# blinkm_mk2v5a.net
KiCad netlist of a schematic drawn in EAGLE
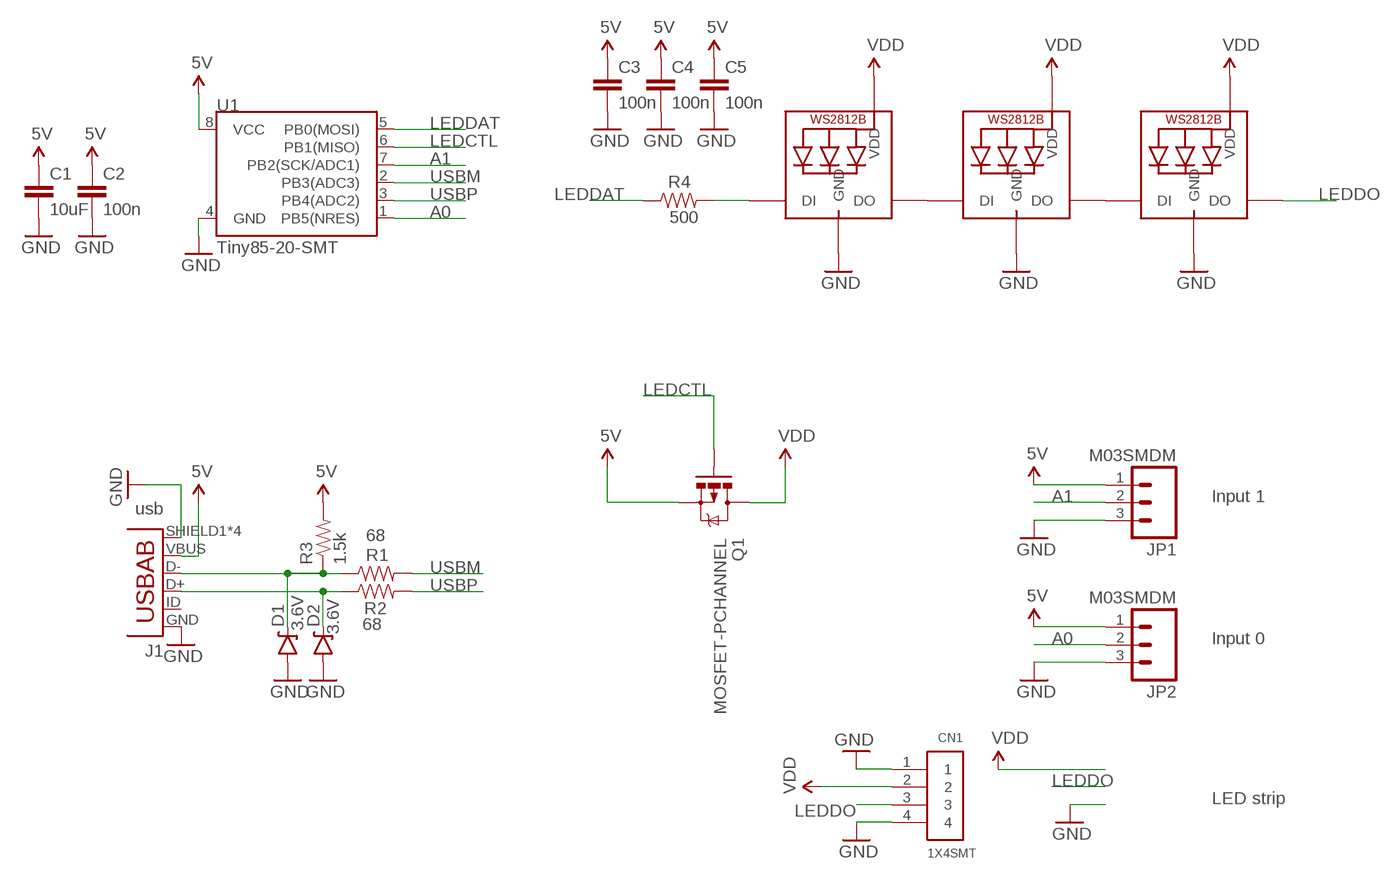
[diagram p0: schematic, sheet 1]

(export (version "E")
  (design (tool "Eeschema 10.0.6"))
  (components
    (comp (ref "C1")
      (value "10uF")
      (footprint "eagle-import:0603-CAP")
      (libsource (lib "eagle-import") (part "CAP0603-CAP"))
    )
    (comp (ref "C2")
      (value "100n")
      (footprint "eagle-import:0603-CAP")
      (libsource (lib "eagle-import") (part "CAP0603-CAP"))
    )
    (comp (ref "C3")
      (value "100n")
      (footprint "eagle-import:0603-CAP")
      (libsource (lib "eagle-import") (part "CAP0603-CAP"))
    )
    (comp (ref "C4")
      (value "100n")
      (footprint "eagle-import:0603-CAP")
      (libsource (lib "eagle-import") (part "CAP0603-CAP"))
    )
    (comp (ref "C5")
      (value "100n")
      (footprint "eagle-import:0603-CAP")
      (libsource (lib "eagle-import") (part "CAP0603-CAP"))
    )
    (comp (ref "CN1")
      (value "1X4SMT")
      (footprint "eagle-import:1X4-SMT")
      (libsource (lib "eagle-import") (part "1X4SMT"))
    )
    (comp (ref "D1")
      (value "3.6V")
      (footprint "eagle-import:SOD-323")
      (libsource (lib "eagle-import") (part "DIODE-ZENER3.3V"))
    )
    (comp (ref "D2")
      (value "3.6V")
      (footprint "eagle-import:SOD-323")
      (libsource (lib "eagle-import") (part "DIODE-ZENER3.3V"))
    )
    (comp (ref "J1")
      (value "usb")
      (footprint "eagle-import:USB-AB-MICRO-SMD")
      (libsource (lib "eagle-import") (part "USB-AB"))
    )
    (comp (ref "JP1")
      (value "M03SMDM")
      (footprint "eagle-import:1X03-SMD-MINIMAL")
      (libsource (lib "eagle-import") (part "M03SMDM"))
    )
    (comp (ref "JP2")
      (value "M03SMDM")
      (footprint "eagle-import:1X03-SMD-MINIMAL")
      (libsource (lib "eagle-import") (part "M03SMDM"))
    )
    (comp (ref "LED1")
      (value "WS2812B3535")
      (footprint "eagle-import:LED3535")
      (libsource (lib "eagle-import") (part "WS2812B3535"))
    )
    (comp (ref "LED2")
      (value "WS2812B3535")
      (footprint "eagle-import:LED3535")
      (libsource (lib "eagle-import") (part "WS2812B3535"))
    )
    (comp (ref "LED3")
      (value "WS2812B3535")
      (footprint "eagle-import:LED3535")
      (libsource (lib "eagle-import") (part "WS2812B3535"))
    )
    (comp (ref "Q1")
      (value "MOSFET-PCHANNEL")
      (footprint "eagle-import:SOT23-3")
      (libsource (lib "eagle-import") (part "MOSFET-PCHANNEL"))
    )
    (comp (ref "R1")
      (value "68")
      (footprint "eagle-import:0603-RES")
      (libsource (lib "eagle-import") (part "RESISTOR0603-RES"))
    )
    (comp (ref "R2")
      (value "68")
      (footprint "eagle-import:0603-RES")
      (libsource (lib "eagle-import") (part "RESISTOR0603-RES"))
    )
    (comp (ref "R3")
      (value "1.5k")
      (footprint "eagle-import:0603-RES")
      (libsource (lib "eagle-import") (part "RESISTOR0603-RES"))
    )
    (comp (ref "R4")
      (value "500")
      (footprint "eagle-import:0603-RES")
      (libsource (lib "eagle-import") (part "RESISTOR0603-RES"))
    )
    (comp (ref "U1")
      (value "Tiny85-20-SMT")
      (footprint "eagle-import:SO08-EIAJ")
      (libsource (lib "eagle-import") (part "ATTINY45TINY85-20-SMT"))
    )
  )
  (nets
    (net (code "1") (name "/A0") (class "Default")
      (node (ref "JP2") (pin "2") (pinfunction "2_2") (pintype "passive"))
      (node (ref "U1") (pin "1") (pinfunction "PB5(NRES)_1") (pintype "bidirectional"))
    )
    (net (code "2") (name "/A1") (class "Default")
      (node (ref "JP1") (pin "2") (pinfunction "2_2") (pintype "passive"))
      (node (ref "U1") (pin "7") (pinfunction "PB2(SCK/ADC1)_7") (pintype "bidirectional"))
    )
    (net (code "3") (name "/LEDCTL") (class "Default")
      (node (ref "Q1") (pin "1") (pinfunction "G_1") (pintype "passive"))
      (node (ref "U1") (pin "6") (pinfunction "PB1(MISO)_6") (pintype "bidirectional"))
    )
    (net (code "4") (name "/LEDDAT") (class "Default")
      (node (ref "R4") (pin "1") (pinfunction "1_1") (pintype "passive"))
      (node (ref "U1") (pin "5") (pinfunction "PB0(MOSI)_5") (pintype "bidirectional"))
    )
    (net (code "5") (name "/LEDDO") (class "Default")
      (node (ref "CN1") (pin "3") (pinfunction "3_3") (pintype "bidirectional"))
      (node (ref "LED3") (pin "3") (pinfunction "DO_3") (pintype "output"))
    )
    (net (code "6") (name "/USBM") (class "Default")
      (node (ref "R1") (pin "2") (pinfunction "2_2") (pintype "passive"))
      (node (ref "U1") (pin "2") (pinfunction "PB3(ADC3)_2") (pintype "bidirectional"))
    )
    (net (code "7") (name "/USBP") (class "Default")
      (node (ref "R2") (pin "2") (pinfunction "2_2") (pintype "passive"))
      (node (ref "U1") (pin "3") (pinfunction "PB4(ADC2)_3") (pintype "bidirectional"))
    )
    (net (code "8") (name "5V") (class "Default")
      (node (ref "C1") (pin "1") (pinfunction "1_1") (pintype "passive"))
      (node (ref "C2") (pin "1") (pinfunction "1_1") (pintype "passive"))
      (node (ref "C3") (pin "1") (pinfunction "1_1") (pintype "passive"))
      (node (ref "C4") (pin "1") (pinfunction "1_1") (pintype "passive"))
      (node (ref "C5") (pin "1") (pinfunction "1_1") (pintype "passive"))
      (node (ref "J1") (pin "VBUS") (pinfunction "VBUS_VBUS") (pintype "bidirectional"))
      (node (ref "JP1") (pin "1") (pinfunction "1_1") (pintype "passive"))
      (node (ref "JP2") (pin "1") (pinfunction "1_1") (pintype "passive"))
      (node (ref "Q1") (pin "2") (pinfunction "S_2") (pintype "passive"))
      (node (ref "R3") (pin "2") (pinfunction "2_2") (pintype "passive"))
      (node (ref "U1") (pin "8") (pinfunction "VCC_8") (pintype "bidirectional"))
    )
    (net (code "9") (name "GND") (class "Default")
      (node (ref "C1") (pin "2") (pinfunction "2_2") (pintype "passive"))
      (node (ref "C2") (pin "2") (pinfunction "2_2") (pintype "passive"))
      (node (ref "C3") (pin "2") (pinfunction "2_2") (pintype "passive"))
      (node (ref "C4") (pin "2") (pinfunction "2_2") (pintype "passive"))
      (node (ref "C5") (pin "2") (pinfunction "2_2") (pintype "passive"))
      (node (ref "CN1") (pin "1") (pinfunction "1_1") (pintype "bidirectional"))
      (node (ref "CN1") (pin "4") (pinfunction "4_4") (pintype "bidirectional"))
      (node (ref "D1") (pin "A") (pinfunction "A_A") (pintype "passive"))
      (node (ref "D2") (pin "A") (pinfunction "A_A") (pintype "passive"))
      (node (ref "J1") (pin "GND") (pinfunction "GND_GND") (pintype "bidirectional"))
      (node (ref "J1") (pin "SHIELD1") (pinfunction "SHIELD_SHIELD1") (pintype "bidirectional"))
      (node (ref "J1") (pin "SHIELD2") (pinfunction "SHIELD_SHIELD2") (pintype "bidirectional"))
      (node (ref "J1") (pin "SHIELD3") (pinfunction "SHIELD_SHIELD3") (pintype "bidirectional"))
      (node (ref "J1") (pin "SHIELD4") (pinfunction "SHIELD_SHIELD4") (pintype "bidirectional"))
      (node (ref "JP1") (pin "3") (pinfunction "3_3") (pintype "passive"))
      (node (ref "JP2") (pin "3") (pinfunction "3_3") (pintype "passive"))
      (node (ref "LED1") (pin "4") (pinfunction "GND_4") (pintype "power_in"))
      (node (ref "LED2") (pin "4") (pinfunction "GND_4") (pintype "power_in"))
      (node (ref "LED3") (pin "4") (pinfunction "GND_4") (pintype "power_in"))
      (node (ref "U1") (pin "4") (pinfunction "GND_4") (pintype "bidirectional"))
    )
    (net (code "10") (name "Net-(D1-PadC)") (class "Default")
      (node (ref "D1") (pin "C") (pinfunction "C_C") (pintype "passive"))
      (node (ref "J1") (pin "D-") (pinfunction "D-_D-") (pintype "bidirectional"))
      (node (ref "R1") (pin "1") (pinfunction "1_1") (pintype "passive"))
      (node (ref "R3") (pin "1") (pinfunction "1_1") (pintype "passive"))
    )
    (net (code "11") (name "Net-(D2-PadC)") (class "Default")
      (node (ref "D2") (pin "C") (pinfunction "C_C") (pintype "passive"))
      (node (ref "J1") (pin "D+") (pinfunction "D+_D+") (pintype "bidirectional"))
      (node (ref "R2") (pin "1") (pinfunction "1_1") (pintype "passive"))
    )
    (net (code "12") (name "Net-(LED1-DI)") (class "Default")
      (node (ref "LED1") (pin "1") (pinfunction "DI_1") (pintype "input"))
      (node (ref "R4") (pin "2") (pinfunction "2_2") (pintype "passive"))
    )
    (net (code "13") (name "Net-(LED1-DO)") (class "Default")
      (node (ref "LED1") (pin "3") (pinfunction "DO_3") (pintype "output"))
      (node (ref "LED2") (pin "1") (pinfunction "DI_1") (pintype "input"))
    )
    (net (code "14") (name "Net-(LED2-DO)") (class "Default")
      (node (ref "LED2") (pin "3") (pinfunction "DO_3") (pintype "output"))
      (node (ref "LED3") (pin "1") (pinfunction "DI_1") (pintype "input"))
    )
    (net (code "15") (name "VDD") (class "Default")
      (node (ref "CN1") (pin "2") (pinfunction "2_2") (pintype "bidirectional"))
      (node (ref "LED1") (pin "2") (pinfunction "VDD_2") (pintype "power_in"))
      (node (ref "LED2") (pin "2") (pinfunction "VDD_2") (pintype "power_in"))
      (node (ref "LED3") (pin "2") (pinfunction "VDD_2") (pintype "power_in"))
      (node (ref "Q1") (pin "3") (pinfunction "D_3") (pintype "passive"))
    )
    (net (code "16") (name "unconnected-(J1-USBID-PadID)") (class "Default")
      (node (ref "J1") (pin "ID") (pinfunction "USBID_ID") (pintype "bidirectional"))
    )
  )
)
